# FFT.net
KiCad netlist of a schematic drawn in Altium Designer
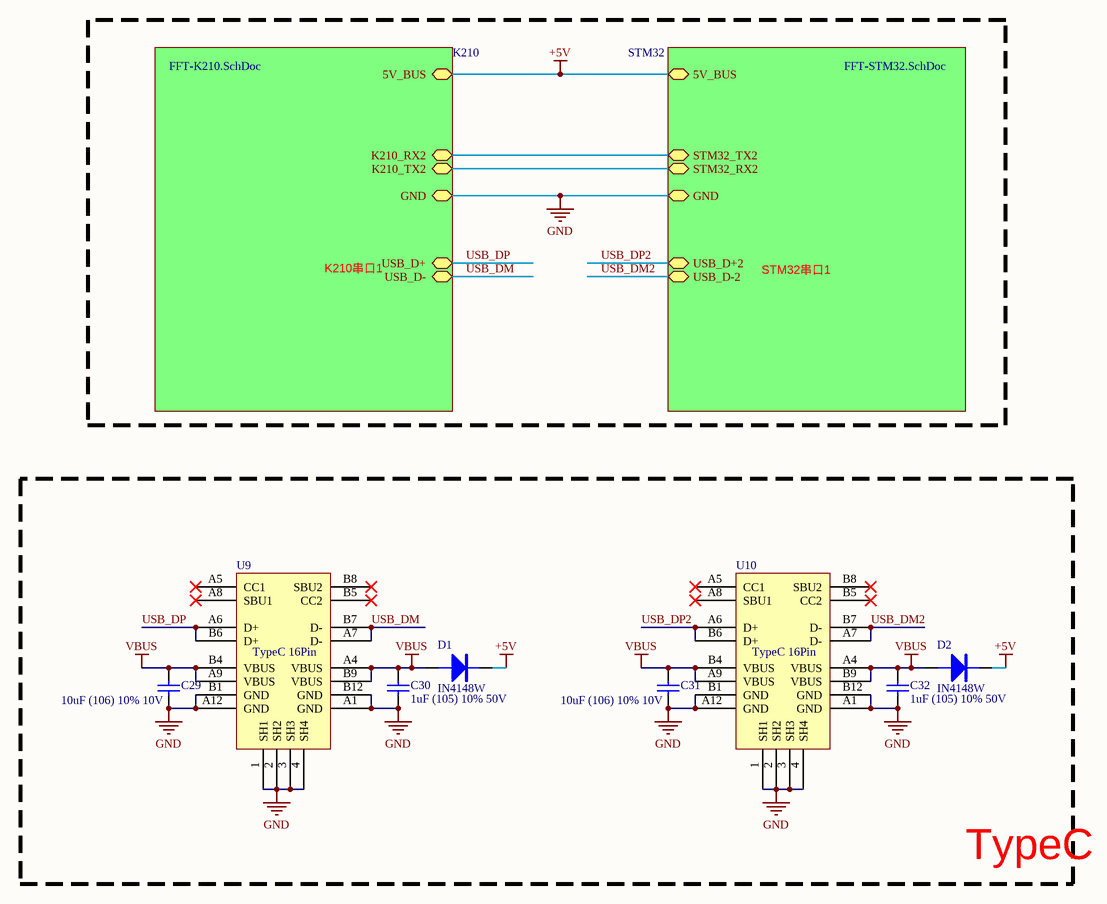
[diagram p0: FFT.SchDoc]

(export (version "E")
  (design (tool "Eeschema 10.0.6"))
  (components
    (comp (ref "C29")
      (value "10uF (106) 10% 10V")
      (footprint "LC-0603_C")
      (description "贴片电容")
      (libsource (lib "Miscellaneous Devices LC") (part "0603 10uF (106) 10% 10V"))
    )
    (comp (ref "C30")
      (value "1uF (105) 10% 50V")
      (footprint "LC-0603_C")
      (description "贴片电容")
      (libsource (lib "Miscellaneous Devices LC") (part "0603 1uF (105) 10% 50V"))
    )
    (comp (ref "C31")
      (value "10uF (106) 10% 10V")
      (footprint "LC-0603_C")
      (description "贴片电容")
      (libsource (lib "Miscellaneous Devices LC") (part "0603 10uF (106) 10% 10V"))
    )
    (comp (ref "C32")
      (value "1uF (105) 10% 50V")
      (footprint "LC-0603_C")
      (description "贴片电容")
      (libsource (lib "Miscellaneous Devices LC") (part "0603 1uF (105) 10% 50V"))
    )
    (comp (ref "D1")
      (value "IN4148W")
      (footprint "SOD-123")
      (description "开关二极管")
      (libsource (lib "二极管") (part "DIODE"))
    )
    (comp (ref "D2")
      (value "IN4148W")
      (footprint "SOD-123")
      (description "开关二极管")
      (libsource (lib "二极管") (part "DIODE"))
    )
    (comp (ref "U9") (value "TypeC 16Pin") (footprint "Type-C") (libsource (lib "AD三维集成库") (part "TypeC")))
    (comp (ref "U10") (value "TypeC 16Pin") (footprint "Type-C") (libsource (lib "AD三维集成库") (part "TypeC")))
  )
  (nets
    (net (code "1") (name "+5V") (class "Default")
      (node (ref "D1") (pin "K") (pinfunction "K_K") (pintype "passive"))
      (node (ref "D2") (pin "K") (pinfunction "K_K") (pintype "passive"))
    )
    (net (code "4") (name "/USB_DM") (class "Default")
      (node (ref "U9") (pin "A7") (pinfunction "D-_A7") (pintype "passive"))
      (node (ref "U9") (pin "B7") (pinfunction "D-_B7") (pintype "passive"))
    )
    (net (code "5") (name "/USB_DM2") (class "Default")
      (node (ref "U10") (pin "A7") (pinfunction "D-_A7") (pintype "passive"))
      (node (ref "U10") (pin "B7") (pinfunction "D-_B7") (pintype "passive"))
    )
    (net (code "6") (name "/USB_DP") (class "Default")
      (node (ref "U9") (pin "A6") (pinfunction "D+_A6") (pintype "passive"))
      (node (ref "U9") (pin "B6") (pinfunction "D+_B6") (pintype "passive"))
    )
    (net (code "7") (name "/USB_DP2") (class "Default")
      (node (ref "U10") (pin "A6") (pinfunction "D+_A6") (pintype "passive"))
      (node (ref "U10") (pin "B6") (pinfunction "D+_B6") (pintype "passive"))
    )
    (net (code "8") (name "GND") (class "Default")
      (node (ref "C29") (pin "1") (pinfunction "1_1") (pintype "passive"))
      (node (ref "C30") (pin "1") (pinfunction "1_1") (pintype "passive"))
      (node (ref "C31") (pin "1") (pinfunction "1_1") (pintype "passive"))
      (node (ref "C32") (pin "1") (pinfunction "1_1") (pintype "passive"))
      (node (ref "U10") (pin "1") (pinfunction "SH1_1") (pintype "passive"))
      (node (ref "U10") (pin "2") (pinfunction "SH2_2") (pintype "passive"))
      (node (ref "U10") (pin "3") (pinfunction "SH3_3") (pintype "passive"))
      (node (ref "U10") (pin "4") (pinfunction "SH4_4") (pintype "passive"))
      (node (ref "U10") (pin "A1") (pinfunction "GND_A1") (pintype "passive"))
      (node (ref "U10") (pin "A12") (pinfunction "GND_A12") (pintype "passive"))
      (node (ref "U10") (pin "B1") (pinfunction "GND_B1") (pintype "passive"))
      (node (ref "U10") (pin "B12") (pinfunction "GND_B12") (pintype "passive"))
      (node (ref "U9") (pin "1") (pinfunction "SH1_1") (pintype "passive"))
      (node (ref "U9") (pin "2") (pinfunction "SH2_2") (pintype "passive"))
      (node (ref "U9") (pin "3") (pinfunction "SH3_3") (pintype "passive"))
      (node (ref "U9") (pin "4") (pinfunction "SH4_4") (pintype "passive"))
      (node (ref "U9") (pin "A1") (pinfunction "GND_A1") (pintype "passive"))
      (node (ref "U9") (pin "A12") (pinfunction "GND_A12") (pintype "passive"))
      (node (ref "U9") (pin "B1") (pinfunction "GND_B1") (pintype "passive"))
      (node (ref "U9") (pin "B12") (pinfunction "GND_B12") (pintype "passive"))
    )
    (net (code "9") (name "VBUS") (class "Default")
      (node (ref "C29") (pin "2") (pinfunction "2_2") (pintype "passive"))
      (node (ref "C30") (pin "2") (pinfunction "2_2") (pintype "passive"))
      (node (ref "C31") (pin "2") (pinfunction "2_2") (pintype "passive"))
      (node (ref "C32") (pin "2") (pinfunction "2_2") (pintype "passive"))
      (node (ref "D1") (pin "A") (pinfunction "A_A") (pintype "passive"))
      (node (ref "D2") (pin "A") (pinfunction "A_A") (pintype "passive"))
      (node (ref "U10") (pin "A4") (pinfunction "VBUS_A4") (pintype "passive"))
      (node (ref "U10") (pin "A9") (pinfunction "VBUS_A9") (pintype "passive"))
      (node (ref "U10") (pin "B4") (pinfunction "VBUS_B4") (pintype "passive"))
      (node (ref "U10") (pin "B9") (pinfunction "VBUS_B9") (pintype "passive"))
      (node (ref "U9") (pin "A4") (pinfunction "VBUS_A4") (pintype "passive"))
      (node (ref "U9") (pin "A9") (pinfunction "VBUS_A9") (pintype "passive"))
      (node (ref "U9") (pin "B4") (pinfunction "VBUS_B4") (pintype "passive"))
      (node (ref "U9") (pin "B9") (pinfunction "VBUS_B9") (pintype "passive"))
    )
    (net (code "10") (name "unconnected-(U9-CC1-PadA5)") (class "Default")
      (node (ref "U9") (pin "A5") (pinfunction "CC1_A5") (pintype "passive+no_connect"))
    )
    (net (code "11") (name "unconnected-(U9-CC2-PadB5)") (class "Default")
      (node (ref "U9") (pin "B5") (pinfunction "CC2_B5") (pintype "passive+no_connect"))
    )
    (net (code "12") (name "unconnected-(U9-SBU1-PadA8)") (class "Default")
      (node (ref "U9") (pin "A8") (pinfunction "SBU1_A8") (pintype "passive+no_connect"))
    )
    (net (code "13") (name "unconnected-(U9-SBU2-PadB8)") (class "Default")
      (node (ref "U9") (pin "B8") (pinfunction "SBU2_B8") (pintype "passive+no_connect"))
    )
    (net (code "14") (name "unconnected-(U10-CC1-PadA5)") (class "Default")
      (node (ref "U10") (pin "A5") (pinfunction "CC1_A5") (pintype "passive+no_connect"))
    )
    (net (code "15") (name "unconnected-(U10-CC2-PadB5)") (class "Default")
      (node (ref "U10") (pin "B5") (pinfunction "CC2_B5") (pintype "passive+no_connect"))
    )
    (net (code "16") (name "unconnected-(U10-SBU1-PadA8)") (class "Default")
      (node (ref "U10") (pin "A8") (pinfunction "SBU1_A8") (pintype "passive+no_connect"))
    )
    (net (code "17") (name "unconnected-(U10-SBU2-PadB8)") (class "Default")
      (node (ref "U10") (pin "B8") (pinfunction "SBU2_B8") (pintype "passive+no_connect"))
    )
  )
)
